# robot.net
KiCad netlist of a schematic drawn in EAGLE
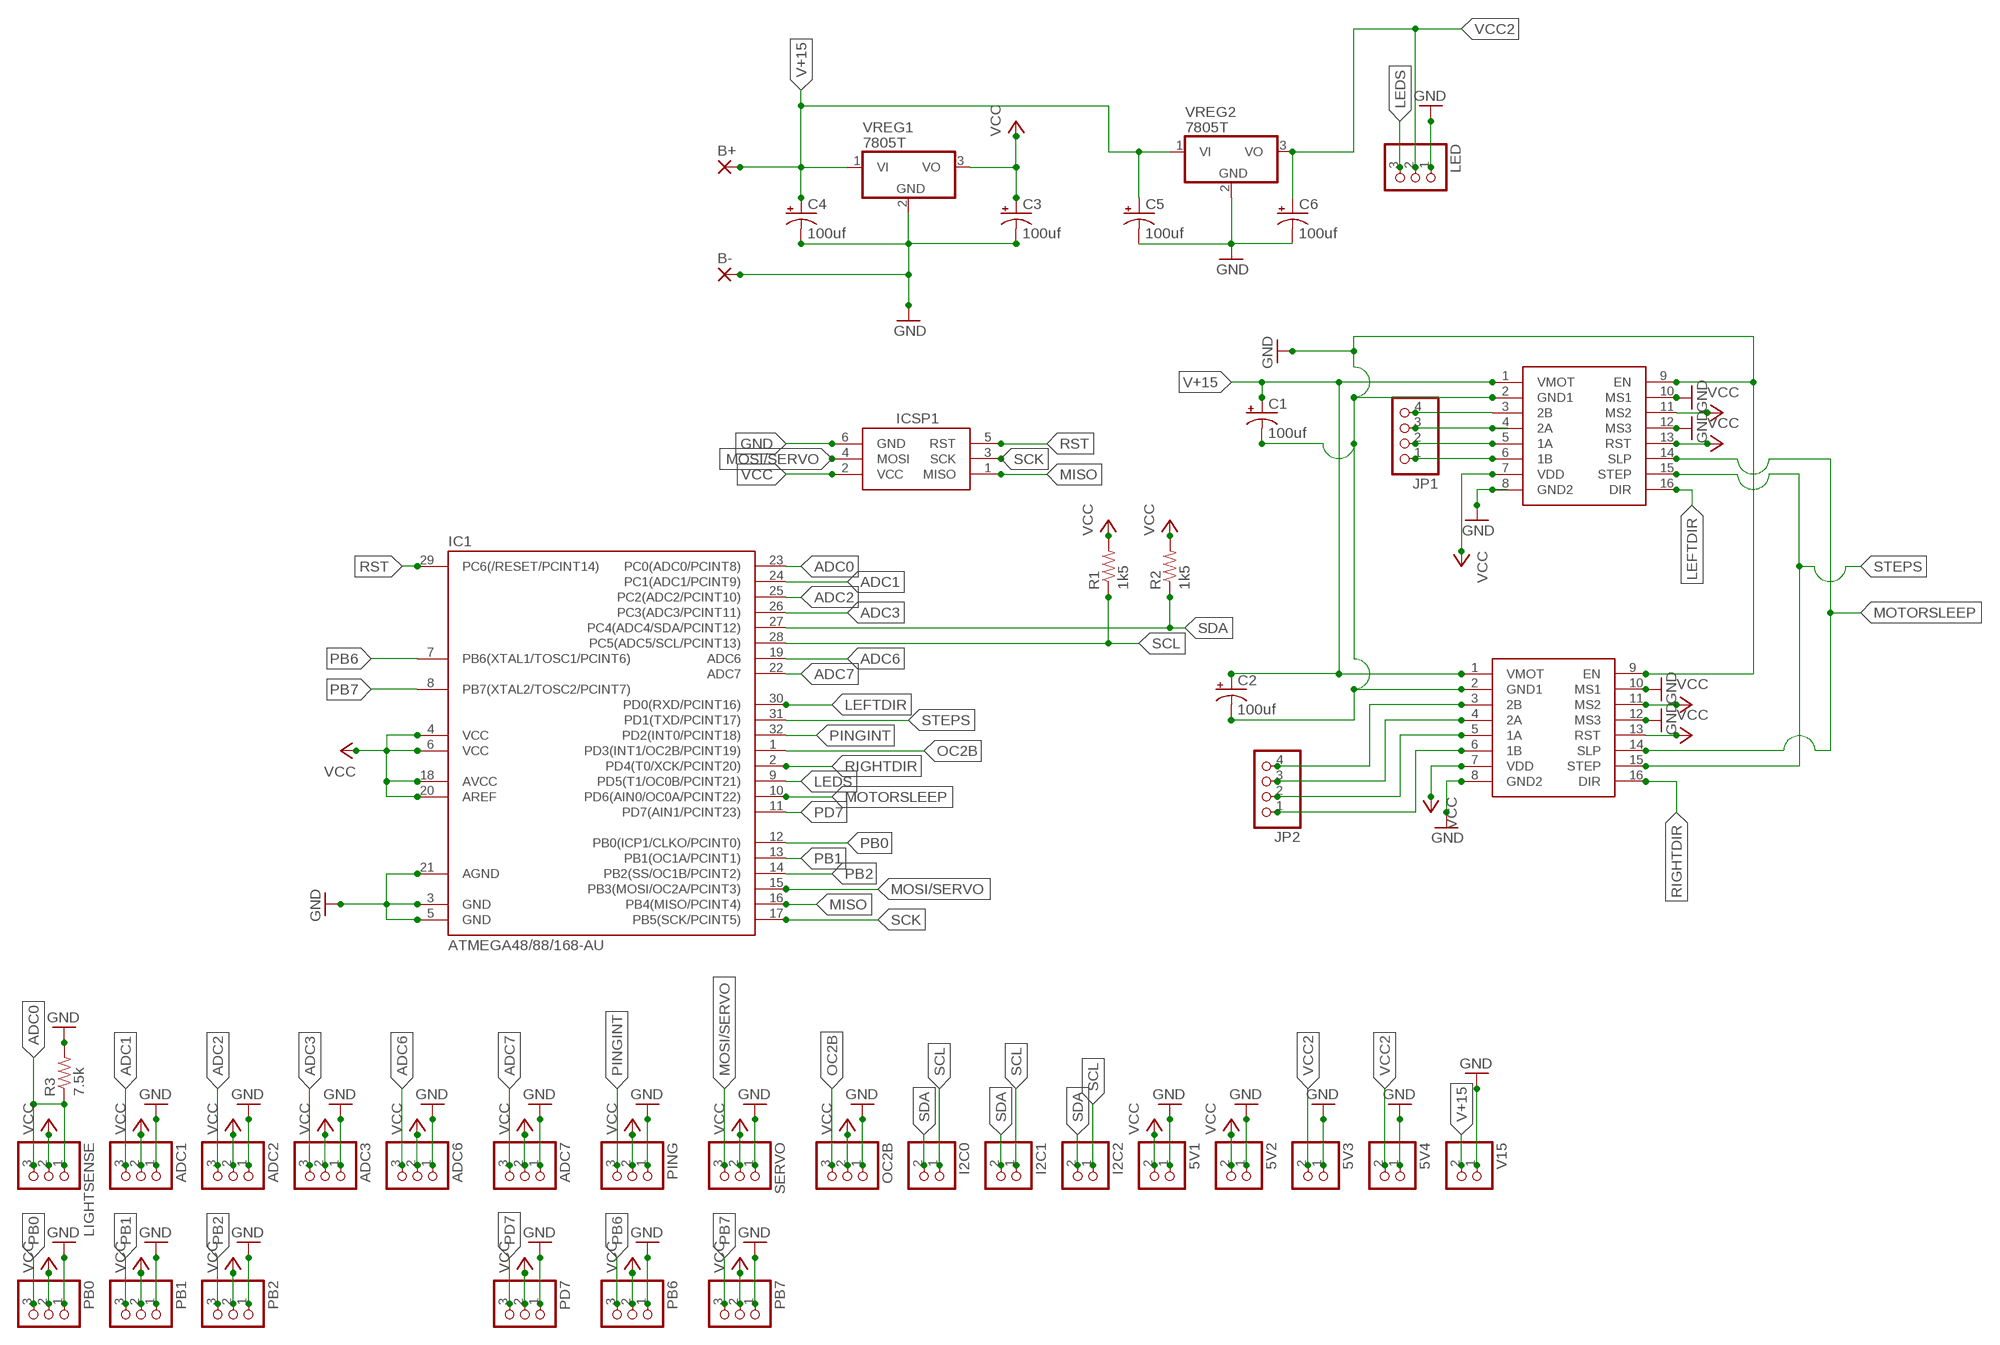
[diagram p0: schematic, sheet 1]

(export (version "E")
  (design (tool "Eeschema 10.0.6"))
  (components
    (comp (ref "5V1")
      (value "PINHD-1X2")
      (footprint "eagle-import:1X02")
      (libsource (lib "eagle-import") (part "PINHD-1X2"))
    )
    (comp (ref "5V2")
      (value "PINHD-1X2")
      (footprint "eagle-import:1X02")
      (libsource (lib "eagle-import") (part "PINHD-1X2"))
    )
    (comp (ref "5V3")
      (value "PINHD-1X2")
      (footprint "eagle-import:1X02")
      (libsource (lib "eagle-import") (part "PINHD-1X2"))
    )
    (comp (ref "5V4")
      (value "PINHD-1X2")
      (footprint "eagle-import:1X02")
      (libsource (lib "eagle-import") (part "PINHD-1X2"))
    )
    (comp (ref "ADC1")
      (value "PINHD-1X3")
      (footprint "eagle-import:1X03")
      (libsource (lib "eagle-import") (part "PINHD-1X3"))
    )
    (comp (ref "ADC2")
      (value "PINHD-1X3")
      (footprint "eagle-import:1X03")
      (libsource (lib "eagle-import") (part "PINHD-1X3"))
    )
    (comp (ref "ADC3")
      (value "PINHD-1X3")
      (footprint "eagle-import:1X03")
      (libsource (lib "eagle-import") (part "PINHD-1X3"))
    )
    (comp (ref "ADC6")
      (value "PINHD-1X3")
      (footprint "eagle-import:1X03")
      (libsource (lib "eagle-import") (part "PINHD-1X3"))
    )
    (comp (ref "ADC7")
      (value "PINHD-1X3")
      (footprint "eagle-import:1X03")
      (libsource (lib "eagle-import") (part "PINHD-1X3"))
    )
    (comp (ref "B+")
      (value "3,81/1,4")
      (footprint "eagle-import:3,81_1,4")
      (libsource (lib "eagle-import") (part "3,81/1,4"))
    )
    (comp (ref "B-")
      (value "3,81/1,4")
      (footprint "eagle-import:3,81_1,4")
      (libsource (lib "eagle-import") (part "3,81/1,4"))
    )
    (comp (ref "C1")
      (value "100uf")
      (footprint "eagle-import:E3,5-8")
      (libsource (lib "eagle-import") (part "CPOL-USE3.5-8"))
    )
    (comp (ref "C2")
      (value "100uf")
      (footprint "eagle-import:E3,5-8")
      (libsource (lib "eagle-import") (part "CPOL-USE3.5-8"))
    )
    (comp (ref "C3")
      (value "100uf")
      (footprint "eagle-import:E3,5-8")
      (libsource (lib "eagle-import") (part "CPOL-USE3.5-8"))
    )
    (comp (ref "C4")
      (value "100uf")
      (footprint "eagle-import:E3,5-8")
      (libsource (lib "eagle-import") (part "CPOL-USE3.5-8"))
    )
    (comp (ref "C5")
      (value "100uf")
      (footprint "eagle-import:E3,5-8")
      (libsource (lib "eagle-import") (part "CPOL-USE3.5-8"))
    )
    (comp (ref "C6")
      (value "100uf")
      (footprint "eagle-import:E3,5-8")
      (libsource (lib "eagle-import") (part "CPOL-USE3.5-8"))
    )
    (comp (ref "I2C0")
      (value "PINHD-1X2")
      (footprint "eagle-import:1X02")
      (libsource (lib "eagle-import") (part "PINHD-1X2"))
    )
    (comp (ref "I2C1")
      (value "PINHD-1X2")
      (footprint "eagle-import:1X02")
      (libsource (lib "eagle-import") (part "PINHD-1X2"))
    )
    (comp (ref "I2C2")
      (value "PINHD-1X2")
      (footprint "eagle-import:1X02")
      (libsource (lib "eagle-import") (part "PINHD-1X2"))
    )
    (comp (ref "IC1")
      (value "ATMEGA48/88/168-AU")
      (footprint "eagle-import:TQFP32-08")
      (libsource (lib "eagle-import") (part "ATMEGA48/88/168-AU"))
    )
    (comp (ref "ICSP1")
      (value "AVRISP-6")
      (footprint "eagle-import:AVRISP")
      (libsource (lib "eagle-import") (part "AVRISP-6"))
    )
    (comp (ref "JP1")
      (value "PINHD-1X4")
      (footprint "eagle-import:1X04")
      (libsource (lib "eagle-import") (part "PINHD-1X4"))
    )
    (comp (ref "JP2")
      (value "PINHD-1X4")
      (footprint "eagle-import:1X04")
      (libsource (lib "eagle-import") (part "PINHD-1X4"))
    )
    (comp (ref "LED")
      (value "PINHD-1X3")
      (footprint "eagle-import:1X03")
      (libsource (lib "eagle-import") (part "PINHD-1X3"))
    )
    (comp (ref "LEFTSTEPPER")
      (value "POLOLUESTEPPERDRIVER")
      (footprint "eagle-import:DIL16")
      (libsource (lib "eagle-import") (part "POLOLUESTEPPERDRIVER"))
    )
    (comp (ref "LIGHTSENSE")
      (value "PINHD-1X3")
      (footprint "eagle-import:1X03")
      (libsource (lib "eagle-import") (part "PINHD-1X3"))
    )
    (comp (ref "OC2B")
      (value "PINHD-1X3")
      (footprint "eagle-import:1X03")
      (libsource (lib "eagle-import") (part "PINHD-1X3"))
    )
    (comp (ref "PB0")
      (value "PINHD-1X3")
      (footprint "eagle-import:1X03")
      (libsource (lib "eagle-import") (part "PINHD-1X3"))
    )
    (comp (ref "PB1")
      (value "PINHD-1X3")
      (footprint "eagle-import:1X03")
      (libsource (lib "eagle-import") (part "PINHD-1X3"))
    )
    (comp (ref "PB2")
      (value "PINHD-1X3")
      (footprint "eagle-import:1X03")
      (libsource (lib "eagle-import") (part "PINHD-1X3"))
    )
    (comp (ref "PB6")
      (value "PINHD-1X3")
      (footprint "eagle-import:1X03")
      (libsource (lib "eagle-import") (part "PINHD-1X3"))
    )
    (comp (ref "PB7")
      (value "PINHD-1X3")
      (footprint "eagle-import:1X03")
      (libsource (lib "eagle-import") (part "PINHD-1X3"))
    )
    (comp (ref "PD7")
      (value "PINHD-1X3")
      (footprint "eagle-import:1X03")
      (libsource (lib "eagle-import") (part "PINHD-1X3"))
    )
    (comp (ref "PING")
      (value "PINHD-1X3")
      (footprint "eagle-import:1X03")
      (libsource (lib "eagle-import") (part "PINHD-1X3"))
    )
    (comp (ref "R1")
      (value "1k5")
      (footprint "eagle-import:M1206")
      (libsource (lib "eagle-import") (part "R-US_M1206"))
    )
    (comp (ref "R2")
      (value "1k5")
      (footprint "eagle-import:M1206")
      (libsource (lib "eagle-import") (part "R-US_M1206"))
    )
    (comp (ref "R3")
      (value "7.5k")
      (footprint "eagle-import:0309_10")
      (libsource (lib "eagle-import") (part "R-US_0309/10"))
    )
    (comp (ref "RIGHTSTEPPER")
      (value "POLOLUESTEPPERDRIVER")
      (footprint "eagle-import:DIL16")
      (libsource (lib "eagle-import") (part "POLOLUESTEPPERDRIVER"))
    )
    (comp (ref "SERVO")
      (value "PINHD-1X3")
      (footprint "eagle-import:1X03")
      (libsource (lib "eagle-import") (part "PINHD-1X3"))
    )
    (comp (ref "V15")
      (value "PINHD-1X2")
      (footprint "eagle-import:1X02")
      (libsource (lib "eagle-import") (part "PINHD-1X2"))
    )
    (comp (ref "VREG1")
      (value "7805T")
      (footprint "eagle-import:TO220H")
      (libsource (lib "eagle-import") (part "78T05"))
    )
    (comp (ref "VREG2")
      (value "7805T")
      (footprint "eagle-import:TO220H")
      (libsource (lib "eagle-import") (part "78T05"))
    )
  )
  (nets
    (net (code "1") (name "ADC0") (class "Default")
      (node (ref "IC1") (pin "23") (pinfunction "PC0(ADC0/PCINT8)_23") (pintype "bidirectional"))
      (node (ref "LIGHTSENSE") (pin "1") (pinfunction "1_1") (pintype "passive"))
      (node (ref "LIGHTSENSE") (pin "3") (pinfunction "3_3") (pintype "passive"))
      (node (ref "R3") (pin "1") (pinfunction "1_1") (pintype "passive"))
    )
    (net (code "2") (name "ADC1") (class "Default")
      (node (ref "ADC1") (pin "3") (pinfunction "3_3") (pintype "passive"))
      (node (ref "IC1") (pin "24") (pinfunction "PC1(ADC1/PCINT9)_24") (pintype "bidirectional"))
    )
    (net (code "3") (name "ADC2") (class "Default")
      (node (ref "ADC2") (pin "3") (pinfunction "3_3") (pintype "passive"))
      (node (ref "IC1") (pin "25") (pinfunction "PC2(ADC2/PCINT10)_25") (pintype "bidirectional"))
    )
    (net (code "4") (name "ADC3") (class "Default")
      (node (ref "ADC3") (pin "3") (pinfunction "3_3") (pintype "passive"))
      (node (ref "IC1") (pin "26") (pinfunction "PC3(ADC3/PCINT11)_26") (pintype "bidirectional"))
    )
    (net (code "5") (name "ADC6") (class "Default")
      (node (ref "ADC6") (pin "3") (pinfunction "3_3") (pintype "passive"))
      (node (ref "IC1") (pin "19") (pinfunction "ADC6_19") (pintype "passive"))
    )
    (net (code "6") (name "ADC7") (class "Default")
      (node (ref "ADC7") (pin "3") (pinfunction "3_3") (pintype "passive"))
      (node (ref "IC1") (pin "22") (pinfunction "ADC7_22") (pintype "passive"))
    )
    (net (code "7") (name "GND") (class "Default")
      (node (ref "5V1") (pin "1") (pinfunction "1_1") (pintype "passive"))
      (node (ref "5V2") (pin "1") (pinfunction "1_1") (pintype "passive"))
      (node (ref "5V3") (pin "1") (pinfunction "1_1") (pintype "passive"))
      (node (ref "5V4") (pin "1") (pinfunction "1_1") (pintype "passive"))
      (node (ref "ADC1") (pin "1") (pinfunction "1_1") (pintype "passive"))
      (node (ref "ADC2") (pin "1") (pinfunction "1_1") (pintype "passive"))
      (node (ref "ADC3") (pin "1") (pinfunction "1_1") (pintype "passive"))
      (node (ref "ADC6") (pin "1") (pinfunction "1_1") (pintype "passive"))
      (node (ref "ADC7") (pin "1") (pinfunction "1_1") (pintype "passive"))
      (node (ref "B-") (pin "1") (pinfunction "P_1") (pintype "passive"))
      (node (ref "C1") (pin "-") (pinfunction "-_-") (pintype "passive"))
      (node (ref "C2") (pin "-") (pinfunction "-_-") (pintype "passive"))
      (node (ref "C3") (pin "-") (pinfunction "-_-") (pintype "passive"))
      (node (ref "C4") (pin "-") (pinfunction "-_-") (pintype "passive"))
      (node (ref "C5") (pin "-") (pinfunction "-_-") (pintype "passive"))
      (node (ref "C6") (pin "-") (pinfunction "-_-") (pintype "passive"))
      (node (ref "IC1") (pin "21") (pinfunction "AGND_21") (pintype "power_in"))
      (node (ref "IC1") (pin "3") (pinfunction "GND_3") (pintype "power_in"))
      (node (ref "IC1") (pin "5") (pinfunction "GND_5") (pintype "power_in"))
      (node (ref "ICSP1") (pin "6") (pinfunction "GND_6") (pintype "power_in"))
      (node (ref "LED") (pin "1") (pinfunction "1_1") (pintype "passive"))
      (node (ref "LEFTSTEPPER") (pin "10") (pinfunction "MS1_10") (pintype "input"))
      (node (ref "LEFTSTEPPER") (pin "12") (pinfunction "MS3_12") (pintype "input"))
      (node (ref "LEFTSTEPPER") (pin "2") (pinfunction "GND1_2") (pintype "power_in"))
      (node (ref "LEFTSTEPPER") (pin "8") (pinfunction "GND2_8") (pintype "power_in"))
      (node (ref "LEFTSTEPPER") (pin "9") (pinfunction "EN_9") (pintype "input"))
      (node (ref "OC2B") (pin "1") (pinfunction "1_1") (pintype "passive"))
      (node (ref "PB0") (pin "1") (pinfunction "1_1") (pintype "passive"))
      (node (ref "PB1") (pin "1") (pinfunction "1_1") (pintype "passive"))
      (node (ref "PB2") (pin "1") (pinfunction "1_1") (pintype "passive"))
      (node (ref "PB6") (pin "1") (pinfunction "1_1") (pintype "passive"))
      (node (ref "PB7") (pin "1") (pinfunction "1_1") (pintype "passive"))
      (node (ref "PD7") (pin "1") (pinfunction "1_1") (pintype "passive"))
      (node (ref "PING") (pin "1") (pinfunction "1_1") (pintype "passive"))
      (node (ref "R3") (pin "2") (pinfunction "2_2") (pintype "passive"))
      (node (ref "RIGHTSTEPPER") (pin "10") (pinfunction "MS1_10") (pintype "input"))
      (node (ref "RIGHTSTEPPER") (pin "12") (pinfunction "MS3_12") (pintype "input"))
      (node (ref "RIGHTSTEPPER") (pin "2") (pinfunction "GND1_2") (pintype "power_in"))
      (node (ref "RIGHTSTEPPER") (pin "8") (pinfunction "GND2_8") (pintype "power_in"))
      (node (ref "RIGHTSTEPPER") (pin "9") (pinfunction "EN_9") (pintype "input"))
      (node (ref "SERVO") (pin "1") (pinfunction "1_1") (pintype "passive"))
      (node (ref "V15") (pin "1") (pinfunction "1_1") (pintype "passive"))
      (node (ref "VREG1") (pin "2") (pinfunction "GND_2") (pintype "passive"))
      (node (ref "VREG2") (pin "2") (pinfunction "GND_2") (pintype "passive"))
    )
    (net (code "8") (name "LEDS") (class "Default")
      (node (ref "IC1") (pin "9") (pinfunction "PD5(T1/OC0B/PCINT21)_9") (pintype "bidirectional"))
      (node (ref "LED") (pin "3") (pinfunction "3_3") (pintype "passive"))
    )
    (net (code "9") (name "LEFTDIR") (class "Default")
      (node (ref "IC1") (pin "30") (pinfunction "PD0(RXD/PCINT16)_30") (pintype "bidirectional"))
      (node (ref "LEFTSTEPPER") (pin "16") (pinfunction "DIR_16") (pintype "input"))
    )
    (net (code "10") (name "MISO") (class "Default")
      (node (ref "IC1") (pin "16") (pinfunction "PB4(MISO/PCINT4)_16") (pintype "bidirectional"))
      (node (ref "ICSP1") (pin "1") (pinfunction "MISO_1") (pintype "input"))
    )
    (net (code "11") (name "MOSI{slash}SERVO") (class "Default")
      (node (ref "IC1") (pin "15") (pinfunction "PB3(MOSI/OC2A/PCINT3)_15") (pintype "bidirectional"))
      (node (ref "ICSP1") (pin "4") (pinfunction "MOSI_4") (pintype "output"))
      (node (ref "SERVO") (pin "3") (pinfunction "3_3") (pintype "passive"))
    )
    (net (code "12") (name "MOTORSLEEP") (class "Default")
      (node (ref "IC1") (pin "10") (pinfunction "PD6(AIN0/OC0A/PCINT22)_10") (pintype "bidirectional"))
      (node (ref "LEFTSTEPPER") (pin "14") (pinfunction "SLP_14") (pintype "input"))
      (node (ref "RIGHTSTEPPER") (pin "14") (pinfunction "SLP_14") (pintype "input"))
    )
    (net (code "13") (name "Net-(LEFTSTEPPER-1A)") (class "Default")
      (node (ref "JP1") (pin "2") (pinfunction "2_2") (pintype "passive"))
      (node (ref "LEFTSTEPPER") (pin "5") (pinfunction "1A_5") (pintype "output"))
    )
    (net (code "14") (name "Net-(LEFTSTEPPER-1B)") (class "Default")
      (node (ref "JP1") (pin "1") (pinfunction "1_1") (pintype "passive"))
      (node (ref "LEFTSTEPPER") (pin "6") (pinfunction "1B_6") (pintype "output"))
    )
    (net (code "15") (name "Net-(LEFTSTEPPER-2A)") (class "Default")
      (node (ref "JP1") (pin "3") (pinfunction "3_3") (pintype "passive"))
      (node (ref "LEFTSTEPPER") (pin "4") (pinfunction "2A_4") (pintype "output"))
    )
    (net (code "16") (name "Net-(LEFTSTEPPER-2B)") (class "Default")
      (node (ref "JP1") (pin "4") (pinfunction "4_4") (pintype "passive"))
      (node (ref "LEFTSTEPPER") (pin "3") (pinfunction "2B_3") (pintype "output"))
    )
    (net (code "17") (name "Net-(RIGHTSTEPPER-1A)") (class "Default")
      (node (ref "JP2") (pin "2") (pinfunction "2_2") (pintype "passive"))
      (node (ref "RIGHTSTEPPER") (pin "5") (pinfunction "1A_5") (pintype "output"))
    )
    (net (code "18") (name "Net-(RIGHTSTEPPER-1B)") (class "Default")
      (node (ref "JP2") (pin "1") (pinfunction "1_1") (pintype "passive"))
      (node (ref "RIGHTSTEPPER") (pin "6") (pinfunction "1B_6") (pintype "output"))
    )
    (net (code "19") (name "Net-(RIGHTSTEPPER-2A)") (class "Default")
      (node (ref "JP2") (pin "3") (pinfunction "3_3") (pintype "passive"))
      (node (ref "RIGHTSTEPPER") (pin "4") (pinfunction "2A_4") (pintype "output"))
    )
    (net (code "20") (name "Net-(RIGHTSTEPPER-2B)") (class "Default")
      (node (ref "JP2") (pin "4") (pinfunction "4_4") (pintype "passive"))
      (node (ref "RIGHTSTEPPER") (pin "3") (pinfunction "2B_3") (pintype "output"))
    )
    (net (code "21") (name "OC2B") (class "Default")
      (node (ref "IC1") (pin "1") (pinfunction "PD3(INT1/OC2B/PCINT19)_1") (pintype "bidirectional"))
      (node (ref "OC2B") (pin "3") (pinfunction "3_3") (pintype "passive"))
    )
    (net (code "22") (name "PB0") (class "Default")
      (node (ref "IC1") (pin "12") (pinfunction "PB0(ICP1/CLKO/PCINT0)_12") (pintype "bidirectional"))
      (node (ref "PB0") (pin "3") (pinfunction "3_3") (pintype "passive"))
    )
    (net (code "23") (name "PB1") (class "Default")
      (node (ref "IC1") (pin "13") (pinfunction "PB1(OC1A/PCINT1)_13") (pintype "bidirectional"))
      (node (ref "PB1") (pin "3") (pinfunction "3_3") (pintype "passive"))
    )
    (net (code "24") (name "PB2") (class "Default")
      (node (ref "IC1") (pin "14") (pinfunction "PB2(SS/OC1B/PCINT2)_14") (pintype "bidirectional"))
      (node (ref "PB2") (pin "3") (pinfunction "3_3") (pintype "passive"))
    )
    (net (code "25") (name "PB6") (class "Default")
      (node (ref "IC1") (pin "7") (pinfunction "PB6(XTAL1/TOSC1/PCINT6)_7") (pintype "bidirectional"))
      (node (ref "PB6") (pin "3") (pinfunction "3_3") (pintype "passive"))
    )
    (net (code "26") (name "PB7") (class "Default")
      (node (ref "IC1") (pin "8") (pinfunction "PB7(XTAL2/TOSC2/PCINT7)_8") (pintype "bidirectional"))
      (node (ref "PB7") (pin "3") (pinfunction "3_3") (pintype "passive"))
    )
    (net (code "27") (name "PD7") (class "Default")
      (node (ref "IC1") (pin "11") (pinfunction "PD7(AIN1/PCINT23)_11") (pintype "bidirectional"))
      (node (ref "PD7") (pin "3") (pinfunction "3_3") (pintype "passive"))
    )
    (net (code "28") (name "PINGINT") (class "Default")
      (node (ref "IC1") (pin "32") (pinfunction "PD2(INT0/PCINT18)_32") (pintype "bidirectional"))
      (node (ref "PING") (pin "3") (pinfunction "3_3") (pintype "passive"))
    )
    (net (code "29") (name "RIGHTDIR") (class "Default")
      (node (ref "IC1") (pin "2") (pinfunction "PD4(T0/XCK/PCINT20)_2") (pintype "bidirectional"))
      (node (ref "RIGHTSTEPPER") (pin "16") (pinfunction "DIR_16") (pintype "input"))
    )
    (net (code "30") (name "RST") (class "Default")
      (node (ref "IC1") (pin "29") (pinfunction "PC6(/RESET/PCINT14)_29") (pintype "bidirectional"))
      (node (ref "ICSP1") (pin "5") (pinfunction "RST_5") (pintype "output"))
    )
    (net (code "31") (name "SCK") (class "Default")
      (node (ref "IC1") (pin "17") (pinfunction "PB5(SCK/PCINT5)_17") (pintype "bidirectional"))
      (node (ref "ICSP1") (pin "3") (pinfunction "SCK_3") (pintype "output"))
    )
    (net (code "32") (name "SCL") (class "Default")
      (node (ref "I2C0") (pin "1") (pinfunction "1_1") (pintype "passive"))
      (node (ref "I2C1") (pin "1") (pinfunction "1_1") (pintype "passive"))
      (node (ref "I2C2") (pin "1") (pinfunction "1_1") (pintype "passive"))
      (node (ref "IC1") (pin "28") (pinfunction "PC5(ADC5/SCL/PCINT13)_28") (pintype "bidirectional"))
      (node (ref "R1") (pin "1") (pinfunction "1_1") (pintype "passive"))
    )
    (net (code "33") (name "SDA") (class "Default")
      (node (ref "I2C0") (pin "2") (pinfunction "2_2") (pintype "passive"))
      (node (ref "I2C1") (pin "2") (pinfunction "2_2") (pintype "passive"))
      (node (ref "I2C2") (pin "2") (pinfunction "2_2") (pintype "passive"))
      (node (ref "IC1") (pin "27") (pinfunction "PC4(ADC4/SDA/PCINT12)_27") (pintype "bidirectional"))
      (node (ref "R2") (pin "1") (pinfunction "1_1") (pintype "passive"))
    )
    (net (code "34") (name "STEPS") (class "Default")
      (node (ref "IC1") (pin "31") (pinfunction "PD1(TXD/PCINT17)_31") (pintype "bidirectional"))
      (node (ref "LEFTSTEPPER") (pin "15") (pinfunction "STEP_15") (pintype "input"))
      (node (ref "RIGHTSTEPPER") (pin "15") (pinfunction "STEP_15") (pintype "input"))
    )
    (net (code "35") (name "V+15") (class "Default")
      (node (ref "B+") (pin "1") (pinfunction "P_1") (pintype "passive"))
      (node (ref "C1") (pin "+") (pinfunction "+_+") (pintype "passive"))
      (node (ref "C2") (pin "+") (pinfunction "+_+") (pintype "passive"))
      (node (ref "C4") (pin "+") (pinfunction "+_+") (pintype "passive"))
      (node (ref "C5") (pin "+") (pinfunction "+_+") (pintype "passive"))
      (node (ref "LEFTSTEPPER") (pin "1") (pinfunction "VMOT_1") (pintype "power_in"))
      (node (ref "RIGHTSTEPPER") (pin "1") (pinfunction "VMOT_1") (pintype "power_in"))
      (node (ref "V15") (pin "2") (pinfunction "2_2") (pintype "passive"))
      (node (ref "VREG1") (pin "1") (pinfunction "VI_1") (pintype "input"))
      (node (ref "VREG2") (pin "1") (pinfunction "VI_1") (pintype "input"))
    )
    (net (code "36") (name "VCC") (class "Default")
      (node (ref "5V1") (pin "2") (pinfunction "2_2") (pintype "passive"))
      (node (ref "5V2") (pin "2") (pinfunction "2_2") (pintype "passive"))
      (node (ref "ADC1") (pin "2") (pinfunction "2_2") (pintype "passive"))
      (node (ref "ADC2") (pin "2") (pinfunction "2_2") (pintype "passive"))
      (node (ref "ADC3") (pin "2") (pinfunction "2_2") (pintype "passive"))
      (node (ref "ADC6") (pin "2") (pinfunction "2_2") (pintype "passive"))
      (node (ref "ADC7") (pin "2") (pinfunction "2_2") (pintype "passive"))
      (node (ref "C3") (pin "+") (pinfunction "+_+") (pintype "passive"))
      (node (ref "IC1") (pin "18") (pinfunction "AVCC_18") (pintype "passive"))
      (node (ref "IC1") (pin "20") (pinfunction "AREF_20") (pintype "passive"))
      (node (ref "IC1") (pin "4") (pinfunction "VCC_4") (pintype "power_in"))
      (node (ref "IC1") (pin "6") (pinfunction "VCC_6") (pintype "power_in"))
      (node (ref "ICSP1") (pin "2") (pinfunction "VCC_2") (pintype "power_in"))
      (node (ref "LEFTSTEPPER") (pin "11") (pinfunction "MS2_11") (pintype "input"))
      (node (ref "LEFTSTEPPER") (pin "13") (pinfunction "RST_13") (pintype "input"))
      (node (ref "LEFTSTEPPER") (pin "7") (pinfunction "VDD_7") (pintype "power_in"))
      (node (ref "LIGHTSENSE") (pin "2") (pinfunction "2_2") (pintype "passive"))
      (node (ref "OC2B") (pin "2") (pinfunction "2_2") (pintype "passive"))
      (node (ref "PB0") (pin "2") (pinfunction "2_2") (pintype "passive"))
      (node (ref "PB1") (pin "2") (pinfunction "2_2") (pintype "passive"))
      (node (ref "PB2") (pin "2") (pinfunction "2_2") (pintype "passive"))
      (node (ref "PB6") (pin "2") (pinfunction "2_2") (pintype "passive"))
      (node (ref "PB7") (pin "2") (pinfunction "2_2") (pintype "passive"))
      (node (ref "PD7") (pin "2") (pinfunction "2_2") (pintype "passive"))
      (node (ref "PING") (pin "2") (pinfunction "2_2") (pintype "passive"))
      (node (ref "R1") (pin "2") (pinfunction "2_2") (pintype "passive"))
      (node (ref "R2") (pin "2") (pinfunction "2_2") (pintype "passive"))
      (node (ref "RIGHTSTEPPER") (pin "11") (pinfunction "MS2_11") (pintype "input"))
      (node (ref "RIGHTSTEPPER") (pin "13") (pinfunction "RST_13") (pintype "input"))
      (node (ref "RIGHTSTEPPER") (pin "7") (pinfunction "VDD_7") (pintype "power_in"))
      (node (ref "SERVO") (pin "2") (pinfunction "2_2") (pintype "passive"))
      (node (ref "VREG1") (pin "3") (pinfunction "VO_3") (pintype "passive"))
    )
    (net (code "37") (name "VCC2") (class "Default")
      (node (ref "5V3") (pin "2") (pinfunction "2_2") (pintype "passive"))
      (node (ref "5V4") (pin "2") (pinfunction "2_2") (pintype "passive"))
      (node (ref "C6") (pin "+") (pinfunction "+_+") (pintype "passive"))
      (node (ref "LED") (pin "2") (pinfunction "2_2") (pintype "passive"))
      (node (ref "VREG2") (pin "3") (pinfunction "VO_3") (pintype "passive"))
    )
  )
)
